# PICKIT4-adaptorUPDI-ONLY.net
KiCad netlist of a schematic drawn in EAGLE
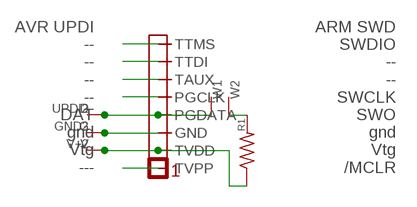
[diagram p0: schematic, sheet 1]

(export (version "E")
  (design (tool "Eeschema 10.0.6"))
  (components
    (comp (ref "D")
      (value "WIRE-R10")
      (footprint "eagle-import:VIA10")
      (libsource (lib "eagle-import") (part "WIRE-R10"))
    )
    (comp (ref "G")
      (value "WIRE-R10")
      (footprint "eagle-import:VIA10")
      (libsource (lib "eagle-import") (part "WIRE-R10"))
    )
    (comp (ref "GND2")
      (value "WIRE-R12")
      (footprint "eagle-import:VIA12")
      (libsource (lib "eagle-import") (part "WIRE-R12"))
    )
    (comp (ref "R1")
      (value "R-US_0204/7")
      (footprint "eagle-import:0204_7")
      (libsource (lib "eagle-import") (part "R-US_0204/7"))
    )
    (comp (ref "U$1")
      (value "PICKIT4PINHDR")
      (footprint "eagle-import:PINHEAD1X8")
      (libsource (lib "eagle-import") (part "PICKIT4PINHDR"))
    )
    (comp (ref "UPDI2")
      (value "WIRE-R12")
      (footprint "eagle-import:VIA12")
      (libsource (lib "eagle-import") (part "WIRE-R12"))
    )
    (comp (ref "V")
      (value "WIRE-R10")
      (footprint "eagle-import:VIA10")
      (libsource (lib "eagle-import") (part "WIRE-R10"))
    )
    (comp (ref "V+2")
      (value "WIRE-R12")
      (footprint "eagle-import:VIA12")
      (libsource (lib "eagle-import") (part "WIRE-R12"))
    )
    (comp (ref "W1")
      (value "WIRE-R10")
      (footprint "eagle-import:VIA10")
      (libsource (lib "eagle-import") (part "WIRE-R10"))
    )
    (comp (ref "W2")
      (value "WIRE-R10")
      (footprint "eagle-import:VIA10")
      (libsource (lib "eagle-import") (part "WIRE-R10"))
    )
  )
  (nets
    (net (code "1") (name "Net-(R1-Pad2)") (class "Default")
      (node (ref "R1") (pin "2") (pinfunction "2_2") (pintype "passive"))
      (node (ref "W2") (pin "P$1") (pinfunction "P$1_P$1") (pintype "bidirectional"))
    )
    (net (code "2") (name "Net-(U$1A-GND)") (class "Default")
      (node (ref "G") (pin "P$1") (pinfunction "P$1_P$1") (pintype "bidirectional"))
      (node (ref "GND2") (pin "P$1") (pinfunction "P$1_P$1") (pintype "bidirectional"))
      (node (ref "U$1") (pin "P$3") (pinfunction "GND_P$3") (pintype "power_in"))
    )
    (net (code "3") (name "Net-(U$1A-PGDATA)") (class "Default")
      (node (ref "D") (pin "P$1") (pinfunction "P$1_P$1") (pintype "bidirectional"))
      (node (ref "U$1") (pin "P$4") (pinfunction "PGDATA_P$4") (pintype "bidirectional"))
      (node (ref "UPDI2") (pin "P$1") (pinfunction "P$1_P$1") (pintype "bidirectional"))
      (node (ref "W1") (pin "P$1") (pinfunction "P$1_P$1") (pintype "bidirectional"))
    )
    (net (code "4") (name "Net-(U$1A-TVDD)") (class "Default")
      (node (ref "R1") (pin "1") (pinfunction "1_1") (pintype "passive"))
      (node (ref "U$1") (pin "P$2") (pinfunction "TVDD_P$2") (pintype "bidirectional"))
      (node (ref "V") (pin "P$1") (pinfunction "P$1_P$1") (pintype "bidirectional"))
      (node (ref "V+2") (pin "P$1") (pinfunction "P$1_P$1") (pintype "bidirectional"))
    )
    (net (code "5") (name "unconnected-(U$1A-PGCLK-PadP$5)") (class "Default")
      (node (ref "U$1") (pin "P$5") (pinfunction "PGCLK_P$5") (pintype "bidirectional"))
    )
    (net (code "6") (name "unconnected-(U$1A-TAUX-PadP$6)") (class "Default")
      (node (ref "U$1") (pin "P$6") (pinfunction "TAUX_P$6") (pintype "bidirectional"))
    )
    (net (code "7") (name "unconnected-(U$1A-TTDI-PadP$7)") (class "Default")
      (node (ref "U$1") (pin "P$7") (pinfunction "TTDI_P$7") (pintype "bidirectional"))
    )
    (net (code "8") (name "unconnected-(U$1A-TTMS-PadP$8)") (class "Default")
      (node (ref "U$1") (pin "P$8") (pinfunction "TTMS_P$8") (pintype "bidirectional"))
    )
    (net (code "9") (name "unconnected-(U$1A-TVPP-PadP$1)") (class "Default")
      (node (ref "U$1") (pin "P$1") (pinfunction "TVPP_P$1") (pintype "bidirectional"))
    )
  )
)
